# SCH_555-Circuit.net
KiCad netlist of a schematic drawn in EasyEDA
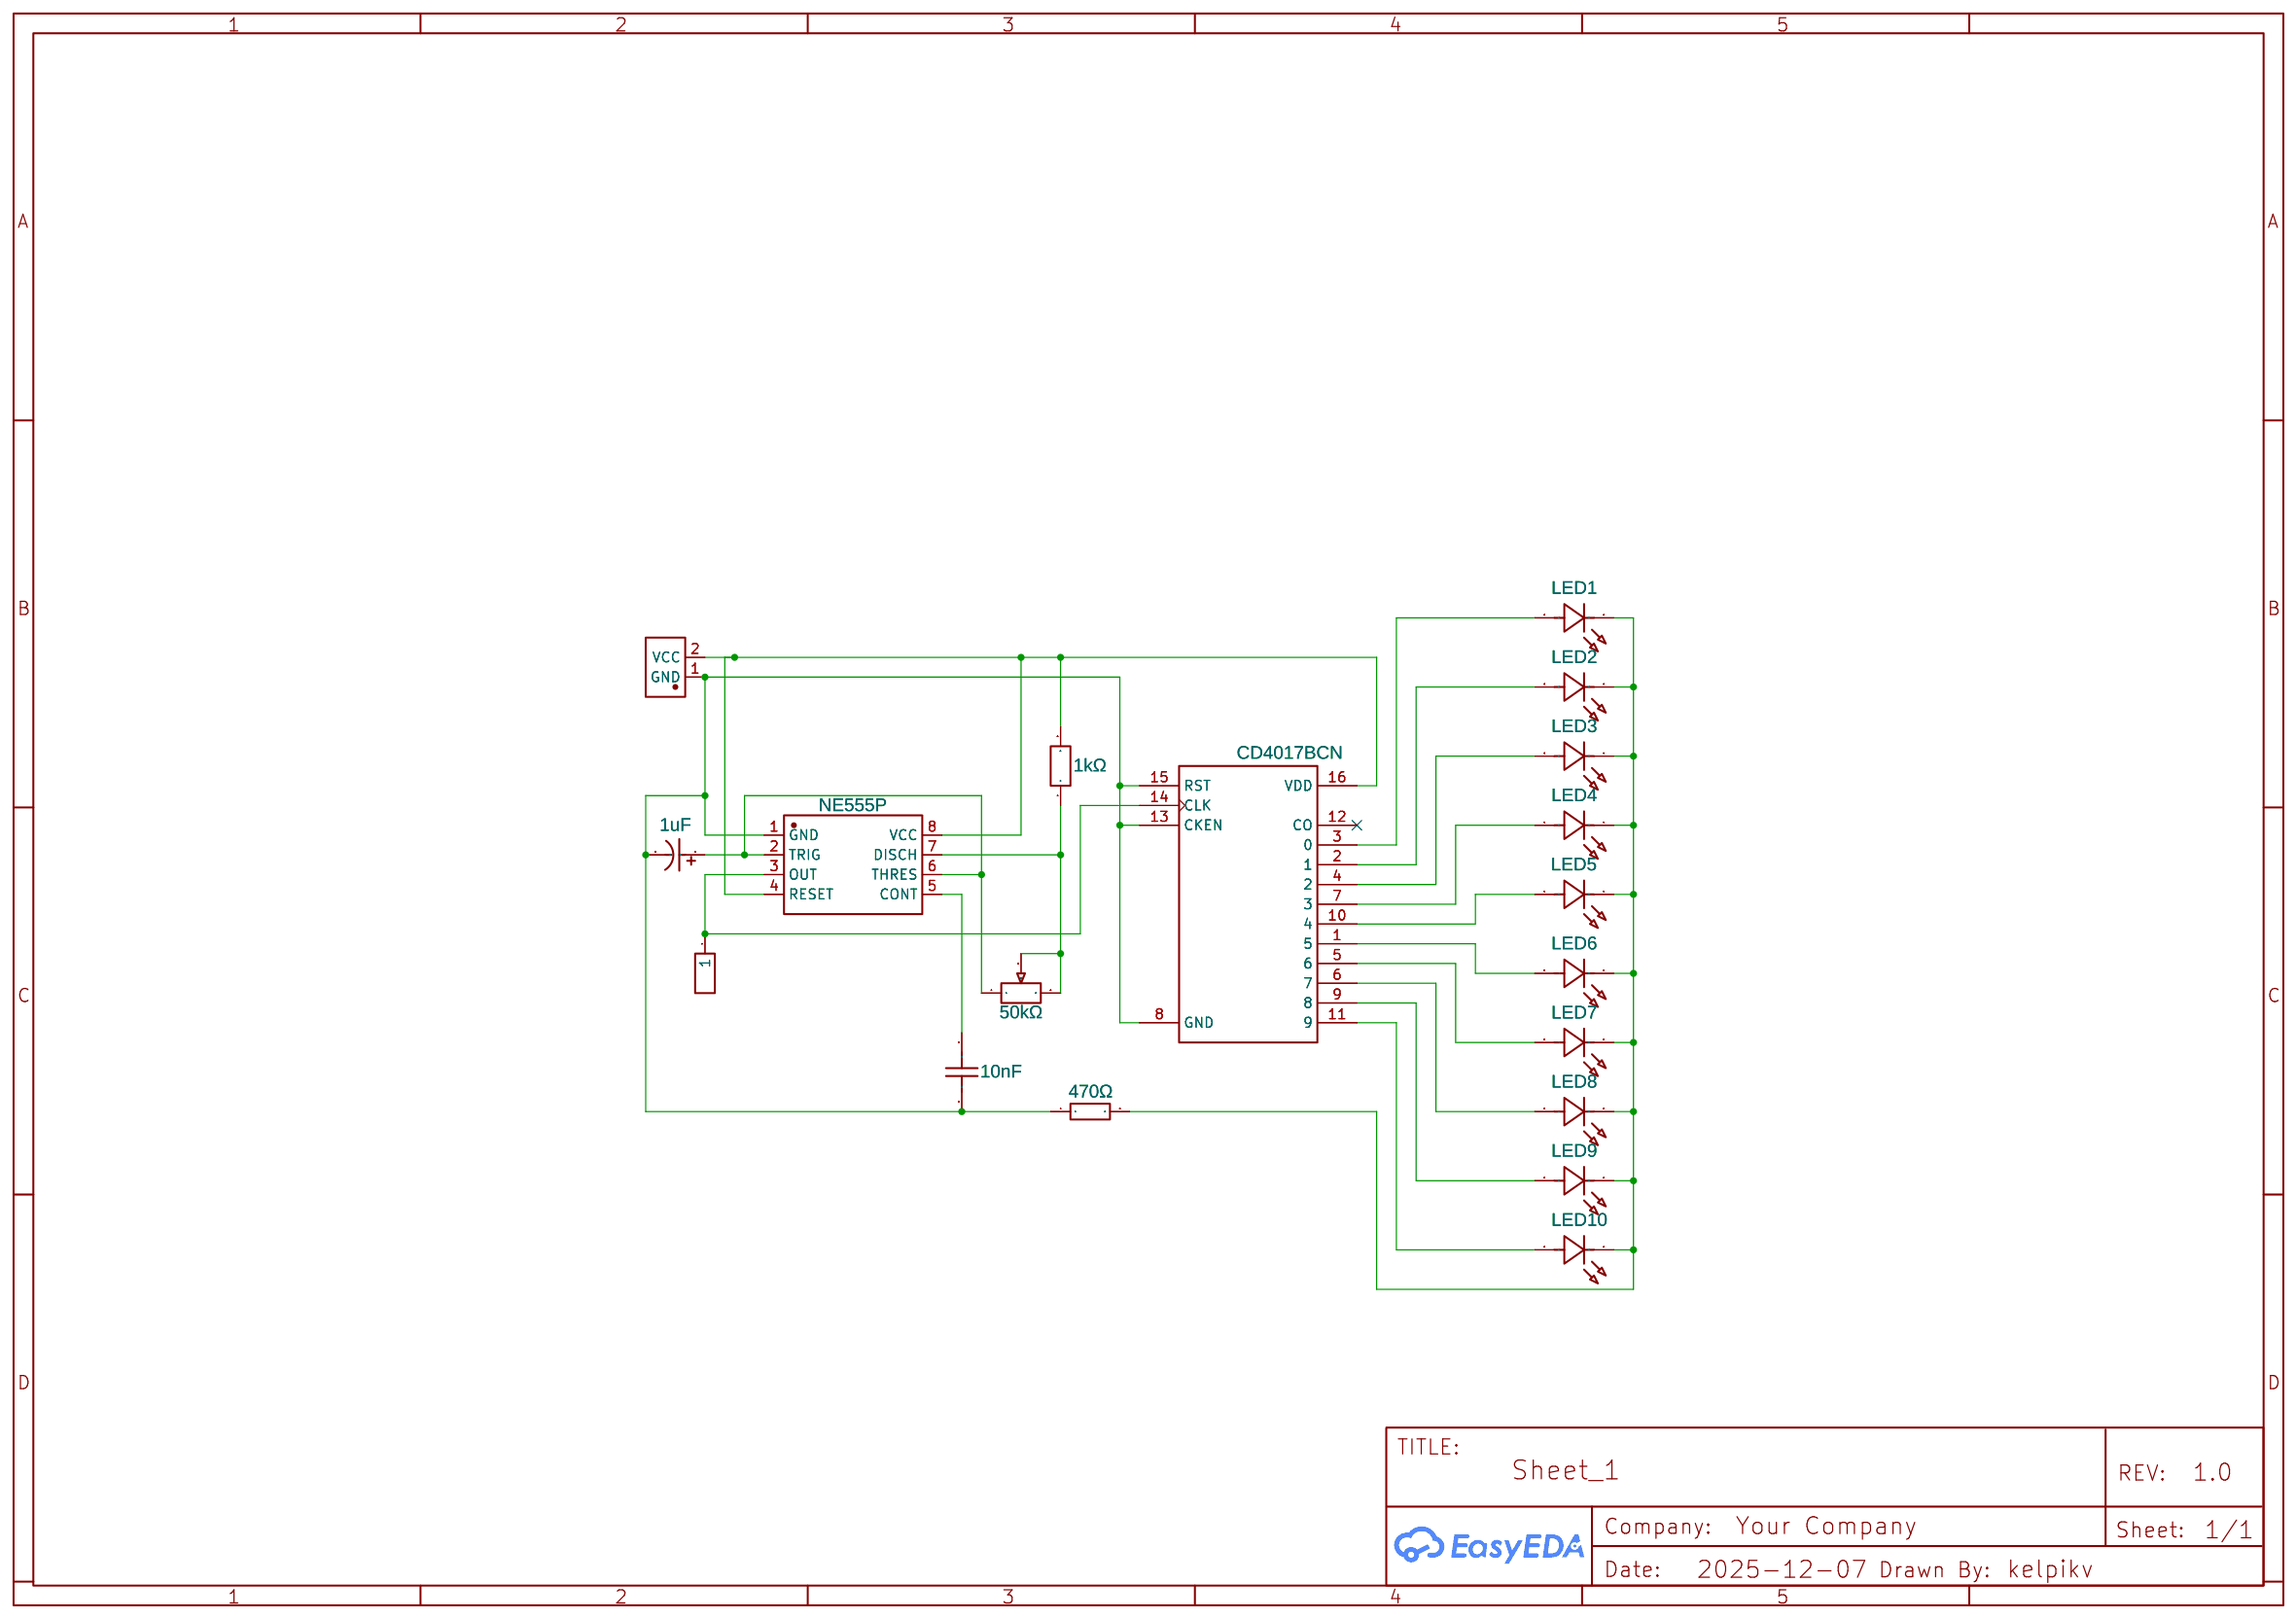
[diagram p0: schematic sheet]

(export (version "E")
  (design (tool "Eeschema 10.0.6"))
  (components
    (comp (ref "C1")
      (value "1uF")
      (fields (field (name "Manufacturer Part") "KF010M050C110A") (field (name "Manufacturer") "CapXon(丰宾)"))
      (libsource (lib "") (part "KF010M050C110A"))
    )
    (comp (ref "C2")
      (value "10nF")
      (fields (field (name "Manufacturer Part") "N09F1B103MN0B0S0N0") (field (name "Manufacturer") "STE(松田)"))
      (libsource (lib "") (part "N09F1B103MN0B0S0N0"))
    )
    (comp (ref "CLK")
      (value "Header-Male-2.54_1x1")
      (fields (field (name "Manufacturer Part") "2.54-1*1P针") (field (name "Manufacturer") "BOOMELE(博穆精密)"))
      (libsource (lib "") (part "Header-Male-2.54_1x1"))
    )
    (comp (ref "HEADER")
      (value "PZ254V-11-02P")
      (fields (field (name "Manufacturer") "XFCN(兴飞)"))
      (libsource (lib "") (part "PZ254V-11-02P"))
    )
    (comp (ref "LED1")
      (value "XL-502UWC")
      (fields (field (name "Manufacturer") "XINGLIGHT(成兴光)"))
      (libsource (lib "") (part "XL-502UWC"))
    )
    (comp (ref "LED2")
      (value "XL-502UWC")
      (fields (field (name "Manufacturer") "XINGLIGHT(成兴光)"))
      (libsource (lib "") (part "XL-502UWC"))
    )
    (comp (ref "LED3")
      (value "XL-502UWC")
      (fields (field (name "Manufacturer") "XINGLIGHT(成兴光)"))
      (libsource (lib "") (part "XL-502UWC"))
    )
    (comp (ref "LED4")
      (value "XL-502UWC")
      (fields (field (name "Manufacturer") "XINGLIGHT(成兴光)"))
      (libsource (lib "") (part "XL-502UWC"))
    )
    (comp (ref "LED5")
      (value "XL-502UWC")
      (fields (field (name "Manufacturer") "XINGLIGHT(成兴光)"))
      (libsource (lib "") (part "XL-502UWC"))
    )
    (comp (ref "LED6")
      (value "XL-502UWC")
      (fields (field (name "Manufacturer") "XINGLIGHT(成兴光)"))
      (libsource (lib "") (part "XL-502UWC"))
    )
    (comp (ref "LED7")
      (value "XL-502UWC")
      (fields (field (name "Manufacturer") "XINGLIGHT(成兴光)"))
      (libsource (lib "") (part "XL-502UWC"))
    )
    (comp (ref "LED8")
      (value "XL-502UWC")
      (fields (field (name "Manufacturer") "XINGLIGHT(成兴光)"))
      (libsource (lib "") (part "XL-502UWC"))
    )
    (comp (ref "LED9")
      (value "XL-502UWC")
      (fields (field (name "Manufacturer") "XINGLIGHT(成兴光)"))
      (libsource (lib "") (part "XL-502UWC"))
    )
    (comp (ref "LED10")
      (value "XL-502UWC")
      (fields (field (name "Manufacturer") "XINGLIGHT(成兴光)"))
      (libsource (lib "") (part "XL-502UWC"))
    )
    (comp (ref "R1")
      (value "1kΩ")
      (fields (field (name "Manufacturer Part") "MF1/4W-1KΩ±1%T52") (field (name "Manufacturer") "华星机电"))
      (libsource (lib "") (part "MF1/4W-1KΩ±1%T52"))
    )
    (comp (ref "R2")
      (value "470Ω")
      (fields
        (field (name "Manufacturer Part") "MFR0W4F4700A50")
        (field (name "Manufacturer") "UNI-ROYAL(厚声)")
      )
      (libsource (lib "") (part "MFR0W4F4700A50"))
    )
    (comp (ref "R4")
      (value "50kΩ")
      (fields (field (name "Manufacturer Part") "3296X-1-503") (field (name "Manufacturer") "BOCHEN(博晨)"))
      (libsource (lib "") (part "3296X-1-503_C118912"))
    )
    (comp (ref "U1")
      (value "NE555P")
      (fields (field (name "Manufacturer") "TI(德州仪器)"))
      (libsource (lib "") (part "NE555P"))
    )
    (comp (ref "U2") (value "CD4017BCN") (libsource (lib "") (part "CD4017BCN")))
  )
  (nets
    (net (code "1") (name "Net-(HEADER-GND)") (class "Default")
      (node (ref "C1") (pin "2") (pinfunction "2_2") (pintype "input"))
      (node (ref "C2") (pin "1") (pinfunction "1_1") (pintype "unspecified"))
      (node (ref "HEADER") (pin "1") (pinfunction "GND_1") (pintype "unspecified"))
      (node (ref "R2") (pin "1") (pinfunction "1_1") (pintype "input"))
      (node (ref "U1") (pin "1") (pinfunction "GND_1") (pintype "unspecified"))
      (node (ref "U2") (pin "13") (pinfunction "CKEN_13") (pintype "unspecified"))
      (node (ref "U2") (pin "15") (pinfunction "RST_15") (pintype "unspecified"))
      (node (ref "U2") (pin "8") (pinfunction "GND_8") (pintype "passive"))
    )
    (net (code "2") (name "Net-(HEADER-VCC)") (class "Default")
      (node (ref "HEADER") (pin "2") (pinfunction "VCC_2") (pintype "unspecified"))
      (node (ref "R1") (pin "2") (pinfunction "2_2") (pintype "unspecified"))
      (node (ref "U1") (pin "4") (pinfunction "RESET_4") (pintype "unspecified"))
      (node (ref "U1") (pin "8") (pinfunction "VCC_8") (pintype "unspecified"))
      (node (ref "U2") (pin "16") (pinfunction "VDD_16") (pintype "passive"))
    )
    (net (code "3") (name "Net-(LED1-A)") (class "Default")
      (node (ref "LED1") (pin "2") (pinfunction "A_2") (pintype "unspecified"))
      (node (ref "U2") (pin "3") (pinfunction "0_3") (pintype "output"))
    )
    (net (code "4") (name "Net-(LED1-K)") (class "Default")
      (node (ref "LED1") (pin "1") (pinfunction "K_1") (pintype "unspecified"))
      (node (ref "LED10") (pin "1") (pinfunction "K_1") (pintype "unspecified"))
      (node (ref "LED2") (pin "1") (pinfunction "K_1") (pintype "unspecified"))
      (node (ref "LED3") (pin "1") (pinfunction "K_1") (pintype "unspecified"))
      (node (ref "LED4") (pin "1") (pinfunction "K_1") (pintype "unspecified"))
      (node (ref "LED5") (pin "1") (pinfunction "K_1") (pintype "unspecified"))
      (node (ref "LED6") (pin "1") (pinfunction "K_1") (pintype "unspecified"))
      (node (ref "LED7") (pin "1") (pinfunction "K_1") (pintype "unspecified"))
      (node (ref "LED8") (pin "1") (pinfunction "K_1") (pintype "unspecified"))
      (node (ref "LED9") (pin "1") (pinfunction "K_1") (pintype "unspecified"))
      (node (ref "R2") (pin "2") (pinfunction "2_2") (pintype "input"))
    )
    (net (code "5") (name "Net-(LED2-A)") (class "Default")
      (node (ref "LED2") (pin "2") (pinfunction "A_2") (pintype "unspecified"))
      (node (ref "U2") (pin "2") (pinfunction "1_2") (pintype "output"))
    )
    (net (code "6") (name "Net-(LED3-A)") (class "Default")
      (node (ref "LED3") (pin "2") (pinfunction "A_2") (pintype "unspecified"))
      (node (ref "U2") (pin "4") (pinfunction "2_4") (pintype "output"))
    )
    (net (code "7") (name "Net-(LED4-A)") (class "Default")
      (node (ref "LED4") (pin "2") (pinfunction "A_2") (pintype "unspecified"))
      (node (ref "U2") (pin "7") (pinfunction "3_7") (pintype "output"))
    )
    (net (code "8") (name "Net-(LED5-A)") (class "Default")
      (node (ref "LED5") (pin "2") (pinfunction "A_2") (pintype "unspecified"))
      (node (ref "U2") (pin "10") (pinfunction "4_10") (pintype "output"))
    )
    (net (code "9") (name "Net-(LED6-A)") (class "Default")
      (node (ref "LED6") (pin "2") (pinfunction "A_2") (pintype "unspecified"))
      (node (ref "U2") (pin "1") (pinfunction "5_1") (pintype "output"))
    )
    (net (code "10") (name "Net-(LED7-A)") (class "Default")
      (node (ref "LED7") (pin "2") (pinfunction "A_2") (pintype "unspecified"))
      (node (ref "U2") (pin "5") (pinfunction "6_5") (pintype "output"))
    )
    (net (code "11") (name "Net-(LED8-A)") (class "Default")
      (node (ref "LED8") (pin "2") (pinfunction "A_2") (pintype "unspecified"))
      (node (ref "U2") (pin "6") (pinfunction "7_6") (pintype "output"))
    )
    (net (code "12") (name "Net-(LED9-A)") (class "Default")
      (node (ref "LED9") (pin "2") (pinfunction "A_2") (pintype "unspecified"))
      (node (ref "U2") (pin "9") (pinfunction "8_9") (pintype "output"))
    )
    (net (code "13") (name "Net-(LED10-A)") (class "Default")
      (node (ref "LED10") (pin "2") (pinfunction "A_2") (pintype "unspecified"))
      (node (ref "U2") (pin "11") (pinfunction "9_11") (pintype "output"))
    )
    (net (code "14") (name "Net-(U1-CONT)") (class "Default")
      (node (ref "C2") (pin "2") (pinfunction "2_2") (pintype "unspecified"))
      (node (ref "U1") (pin "5") (pinfunction "CONT_5") (pintype "unspecified"))
    )
    (net (code "15") (name "Net-(U1-DISCH)") (class "Default")
      (node (ref "R1") (pin "1") (pinfunction "1_1") (pintype "unspecified"))
      (node (ref "R4") (pin "2") (pinfunction "2_2") (pintype "input"))
      (node (ref "R4") (pin "3") (pinfunction "3_3") (pintype "input"))
      (node (ref "U1") (pin "7") (pinfunction "DISCH_7") (pintype "unspecified"))
    )
    (net (code "16") (name "Net-(U1-OUT)") (class "Default")
      (node (ref "CLK") (pin "1") (pinfunction "1_1") (pintype "input"))
      (node (ref "U1") (pin "3") (pinfunction "OUT_3") (pintype "unspecified"))
      (node (ref "U2") (pin "14") (pinfunction "CLK_14") (pintype "unspecified"))
    )
    (net (code "17") (name "Net-(U1-THRES)") (class "Default")
      (node (ref "C1") (pin "1") (pinfunction "1_1") (pintype "input"))
      (node (ref "R4") (pin "1") (pinfunction "1_1") (pintype "input"))
      (node (ref "U1") (pin "2") (pinfunction "TRIG_2") (pintype "unspecified"))
      (node (ref "U1") (pin "6") (pinfunction "THRES_6") (pintype "unspecified"))
    )
    (net (code "18") (name "unconnected-(U2-CO-Pad12)") (class "Default")
      (node (ref "U2") (pin "12") (pinfunction "CO_12") (pintype "output+no_connect"))
    )
  )
)
